# 2_-Charger.net
KiCad netlist of a schematic drawn in Altium Designer
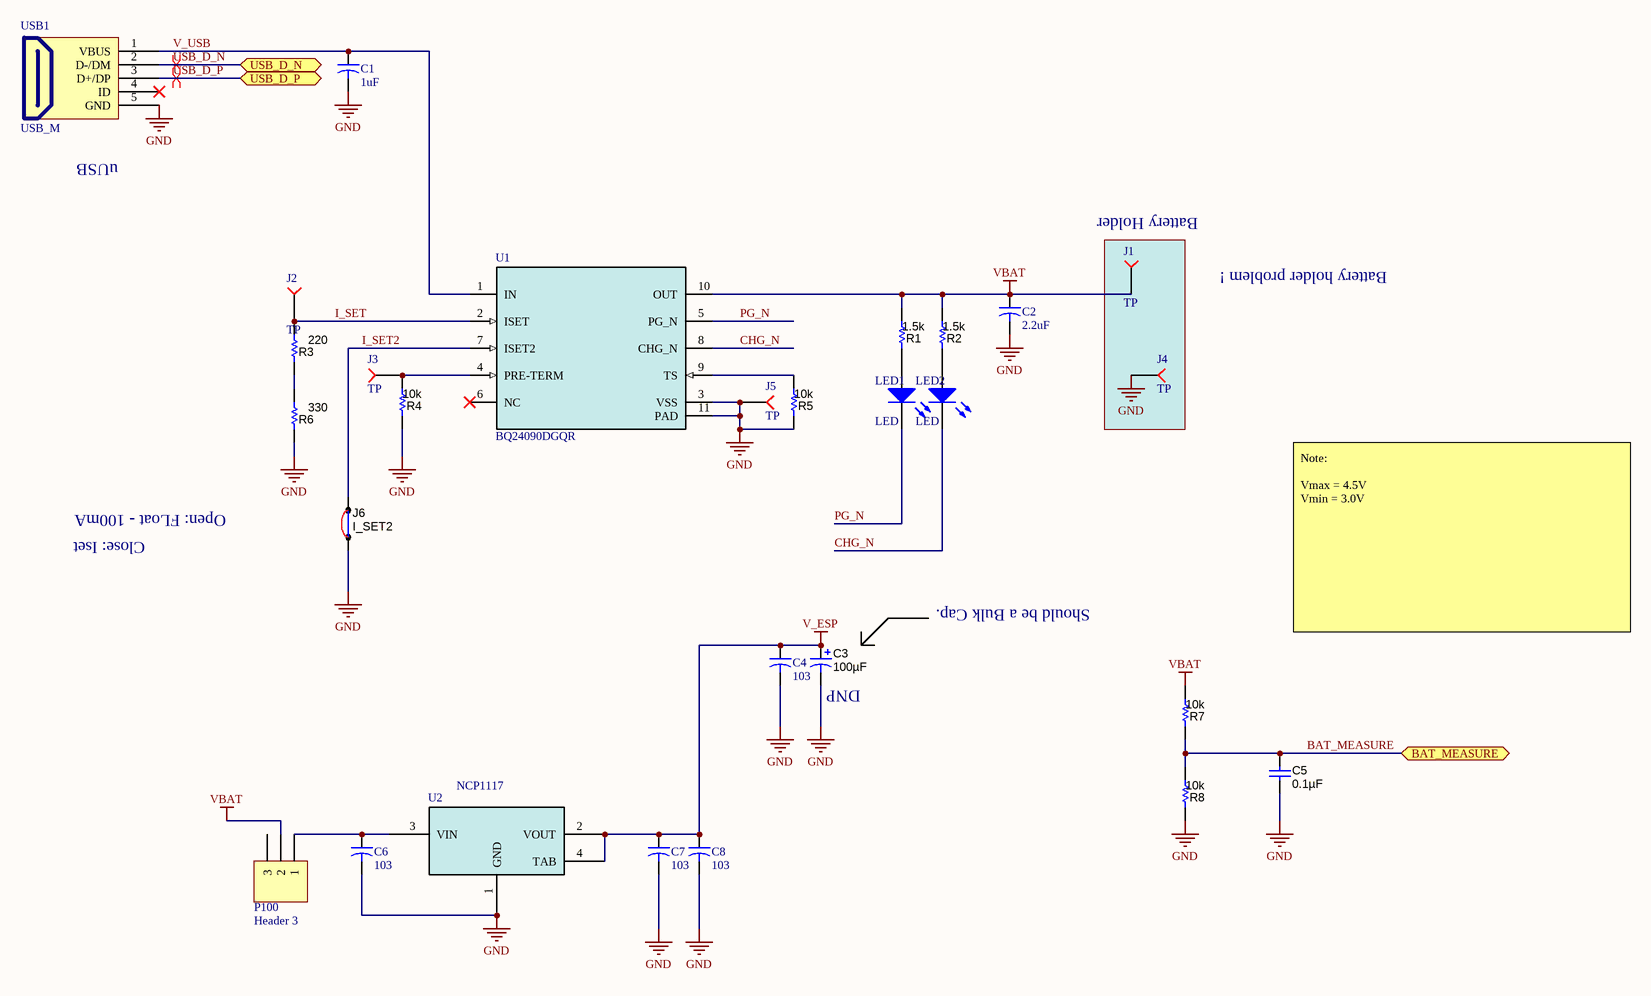
[diagram p0: [2]-Charger.SchDoc]

(export (version "E")
  (design (tool "Eeschema 10.0.6"))
  (components
    (comp (ref "C1")
      (value "1uF")
      (footprint "0603")
      (description "Ceramic")
      (fields (field (name "PUBLISHER") "Altium Limited"))
      (libsource (lib "Capacitor") (part "Cap 0805"))
    )
    (comp (ref "C2")
      (value "2.2uF")
      (footprint "0603")
      (description "Ceramic")
      (fields (field (name "PUBLISHER") "Altium Limited"))
      (libsource (lib "Capacitor") (part "Cap 0805"))
    )
    (comp (ref "C3")
      (value "293D107X96R3B2TE3")
      (footprint "3528-21")
      (description "CAP, TANT, 100uF, 6.3V, +/-10%, 1.7 ohm, 3528-21 SMD")
      (fields
        (field (name "MANUFACTURER") "Vishay-Sprague")
        (field (name "VALUEDISPLAYED") "100µF")
        (field (name "PUBLISHER") "Texas Instruments")
      )
      (libsource (lib "tuongpv2") (part "C_293D107X96R3B2TE3"))
    )
    (comp (ref "C4")
      (value "103")
      (footprint "0603")
      (description "Ceramic")
      (fields (field (name "PUBLISHER") "Altium Limited"))
      (libsource (lib "Capacitor") (part "Cap 0805"))
    )
    (comp (ref "C5")
      (value "0603YC104JAT2A")
      (footprint "0603")
      (description "CAP, CERM, 0.1uF, 16V, +/-5%, X7R, 0603")
      (fields
        (field (name "MANUFACTURER") "AVX")
        (field (name "VALUEDISPLAYED") "0.1µF")
        (field (name "PUBLISHER") "Texas Instruments")
      )
      (libsource (lib "tuongpv2") (part "Cap_0603"))
    )
    (comp (ref "C6")
      (value "103")
      (footprint "0603")
      (description "Ceramic")
      (fields (field (name "PUBLISHER") "Altium Limited"))
      (libsource (lib "Capacitor") (part "Cap 0805"))
    )
    (comp (ref "C7")
      (value "103")
      (footprint "0603")
      (description "Ceramic")
      (fields (field (name "PUBLISHER") "Altium Limited"))
      (libsource (lib "Capacitor") (part "Cap 0805"))
    )
    (comp (ref "C8")
      (value "103")
      (footprint "0603")
      (description "Ceramic")
      (fields (field (name "PUBLISHER") "Altium Limited"))
      (libsource (lib "Capacitor") (part "Cap 0805"))
    )
    (comp (ref "J1")
      (value "TP")
      (footprint "TP")
      (description "Test point (true)")
      (libsource (lib "Cty1") (part "TP"))
    )
    (comp (ref "J2")
      (value "TP")
      (footprint "TP")
      (description "Test point (true)")
      (libsource (lib "Cty1") (part "TP"))
    )
    (comp (ref "J3")
      (value "TP")
      (footprint "TP")
      (description "Test point (true)")
      (libsource (lib "Cty1") (part "TP"))
    )
    (comp (ref "J4")
      (value "TP")
      (footprint "TP")
      (description "Test point (true)")
      (libsource (lib "Cty1") (part "TP"))
    )
    (comp (ref "J5")
      (value "TP")
      (footprint "TP")
      (description "Test point (true)")
      (libsource (lib "Cty1") (part "TP"))
    )
    (comp (ref "J6")
      (value "I_SET2")
      (footprint "HDR1X2")
      (description "Jumper Wire, 200mil spacing, Red, pkg of 200")
      (fields
        (field (name "PARTNUMBER") "923345-02-C")
        (field (name "MANUFACTURER") "3M")
        (field (name "SYMBOLCREATOR") "a0412235")
        (field (name "PUBLISHER") "Texas Instruments")
      )
      (libsource (lib "Connectors") (part "923345-02-C"))
    )
    (comp (ref "LED1")
      (value "LED")
      (footprint "LED-0603-YELLOW")
      (description "Typical INFRARED GaAs LED")
      (fields (field (name "PUBLISHER") "Altium Limited"))
      (libsource (lib "VTEKLib") (part "LED"))
    )
    (comp (ref "LED2")
      (value "LED")
      (footprint "LED-0603-YELLOW")
      (description "Typical INFRARED GaAs LED")
      (fields (field (name "PUBLISHER") "Altium Limited"))
      (libsource (lib "VTEKLib") (part "LED"))
    )
    (comp (ref "P100")
      (value "Header 3")
      (footprint "SW_Slide")
      (description "Header, 3-Pin")
      (fields (field (name "PUBLISHER") "Altium Limited"))
      (libsource (lib "Connecter") (part "Header 3"))
    )
    (comp (ref "R1")
      (value "1.5k")
      (footprint "0603")
      (description "RES 5%, 0.125W, 0805")
      (fields
        (field (name "PARTNUMBER") "CRCW08051K00JNEA")
        (field (name "MANUFACTURER") "Vishay-Dale")
        (field (name "PUBLISHER") "Texas Instruments")
      )
      (libsource (lib "Cty1") (part "R0805_025W"))
    )
    (comp (ref "R2")
      (value "1.5k")
      (footprint "0603")
      (description "RES 5%, 0.125W, 0805")
      (fields
        (field (name "PARTNUMBER") "CRCW08051K00JNEA")
        (field (name "MANUFACTURER") "Vishay-Dale")
        (field (name "PUBLISHER") "Texas Instruments")
      )
      (libsource (lib "Cty1") (part "R0805_025W"))
    )
    (comp (ref "R3")
      (value "220")
      (footprint "0603")
      (description "RES 5%, 0.125W, 0805")
      (fields
        (field (name "PARTNUMBER") "CRCW08051K00JNEA")
        (field (name "MANUFACTURER") "Vishay-Dale")
        (field (name "PUBLISHER") "Texas Instruments")
      )
      (libsource (lib "Cty1") (part "R0805_025W"))
    )
    (comp (ref "R4")
      (value "10k")
      (footprint "0603")
      (description "RES 5%, 0.125W, 0805")
      (fields
        (field (name "PARTNUMBER") "CRCW08051K00JNEA")
        (field (name "MANUFACTURER") "Vishay-Dale")
        (field (name "PUBLISHER") "Texas Instruments")
      )
      (libsource (lib "Cty1") (part "R0805_025W"))
    )
    (comp (ref "R5")
      (value "10k")
      (footprint "0603")
      (description "RES 5%, 0.125W, 0805")
      (fields
        (field (name "PARTNUMBER") "CRCW08051K00JNEA")
        (field (name "MANUFACTURER") "Vishay-Dale")
        (field (name "PUBLISHER") "Texas Instruments")
      )
      (libsource (lib "Cty1") (part "R0805_025W"))
    )
    (comp (ref "R6")
      (value "330")
      (footprint "0603")
      (description "RES 5%, 0.125W, 0805")
      (fields
        (field (name "PARTNUMBER") "CRCW08051K00JNEA")
        (field (name "MANUFACTURER") "Vishay-Dale")
        (field (name "PUBLISHER") "Texas Instruments")
      )
      (libsource (lib "Cty1") (part "R0805_025W"))
    )
    (comp (ref "R7")
      (value "10k")
      (footprint "0603")
      (description "RES 5%, 0.125W, 0805")
      (fields
        (field (name "PARTNUMBER") "CRCW08051K00JNEA")
        (field (name "MANUFACTURER") "Vishay-Dale")
        (field (name "PUBLISHER") "Texas Instruments")
      )
      (libsource (lib "Cty1") (part "R0805_025W"))
    )
    (comp (ref "R8")
      (value "10k")
      (footprint "0603")
      (description "RES 5%, 0.125W, 0805")
      (fields
        (field (name "PARTNUMBER") "CRCW08051K00JNEA")
        (field (name "MANUFACTURER") "Vishay-Dale")
        (field (name "PUBLISHER") "Texas Instruments")
      )
      (libsource (lib "Cty1") (part "R0805_025W"))
    )
    (comp (ref "U1")
      (value "BQ24090DGQR")
      (footprint "DGQ0010D_NV_N")
      (description "Single Cell Li-Ion and Li-Pol Battery Charger")
      (fields
        (field (name "ALTERNATE PARTNUMBER") "BQ24090DGQT")
        (field (name "MANUFACTURER") "Texas Instruments")
      )
      (libsource (lib "SMPS_IC") (part "BQ24090DGQR"))
    )
    (comp (ref "U2")
      (value "NCP1117")
      (footprint "SOT-223B_L")
      (description "1000mA Low-Dropout Positive Fixed and Adjustable Voltage Regulators")
      (fields (field (name "DIGIKEY PART") "NCP1117ST33T3GOSTR-ND"))
      (libsource (lib "SMPS_IC") (part "NCP1117"))
    )
    (comp (ref "USB1") (value "USB_M") (footprint "USB_MICRO_SMD") (libsource (lib "VTEKLib") (part "USB_M")))
  )
  (nets
    (net (code "1") (name "/BAT_MEASURE") (class "Default")
      (node (ref "C5") (pin "1") (pinfunction "1_1") (pintype "passive"))
      (node (ref "R7") (pin "1") (pinfunction "1_1") (pintype "passive"))
      (node (ref "R8") (pin "2") (pinfunction "2_2") (pintype "passive"))
    )
    (net (code "2") (name "/CHG_N") (class "Default")
      (node (ref "LED2") (pin "2") (pinfunction "K_2") (pintype "passive"))
      (node (ref "U1") (pin "8") (pinfunction "CHG_N_8") (pintype "tri_state"))
    )
    (net (code "3") (name "/I_SET") (class "Default")
      (node (ref "J2") (pin "0") (pinfunction "0_0") (pintype "passive"))
      (node (ref "R3") (pin "2") (pinfunction "2_2") (pintype "passive"))
      (node (ref "U1") (pin "2") (pinfunction "ISET_2") (pintype "input"))
    )
    (net (code "4") (name "/I_SET2") (class "Default")
      (node (ref "J6") (pin "2") (pinfunction "2_2") (pintype "passive"))
      (node (ref "U1") (pin "7") (pinfunction "ISET2_7") (pintype "input"))
    )
    (net (code "5") (name "/PG_N") (class "Default")
      (node (ref "LED1") (pin "2") (pinfunction "K_2") (pintype "passive"))
      (node (ref "U1") (pin "5") (pinfunction "PG_N_5") (pintype "tri_state"))
    )
    (net (code "6") (name "/USB_D_N") (class "Default")
      (node (ref "USB1") (pin "2") (pinfunction "D-/DM_2") (pintype "passive"))
    )
    (net (code "7") (name "/USB_D_P") (class "Default")
      (node (ref "USB1") (pin "3") (pinfunction "D+/DP_3") (pintype "passive"))
    )
    (net (code "8") (name "/V_USB") (class "Default")
      (node (ref "C1") (pin "1") (pinfunction "1_1") (pintype "passive"))
      (node (ref "U1") (pin "1") (pinfunction "IN_1") (pintype "power_in"))
      (node (ref "USB1") (pin "1") (pinfunction "VBUS_1") (pintype "passive"))
    )
    (net (code "9") (name "GND") (class "Default")
      (node (ref "C1") (pin "2") (pinfunction "2_2") (pintype "passive"))
      (node (ref "C2") (pin "2") (pinfunction "2_2") (pintype "passive"))
      (node (ref "C3") (pin "2") (pinfunction "-_2") (pintype "passive"))
      (node (ref "C4") (pin "2") (pinfunction "2_2") (pintype "passive"))
      (node (ref "C5") (pin "2") (pinfunction "2_2") (pintype "passive"))
      (node (ref "C6") (pin "2") (pinfunction "2_2") (pintype "passive"))
      (node (ref "C7") (pin "2") (pinfunction "2_2") (pintype "passive"))
      (node (ref "C8") (pin "2") (pinfunction "2_2") (pintype "passive"))
      (node (ref "J4") (pin "0") (pinfunction "0_0") (pintype "passive"))
      (node (ref "J5") (pin "0") (pinfunction "0_0") (pintype "passive"))
      (node (ref "J6") (pin "1") (pinfunction "1_1") (pintype "passive"))
      (node (ref "R4") (pin "1") (pinfunction "1_1") (pintype "passive"))
      (node (ref "R5") (pin "1") (pinfunction "1_1") (pintype "passive"))
      (node (ref "R6") (pin "1") (pinfunction "1_1") (pintype "passive"))
      (node (ref "R8") (pin "1") (pinfunction "1_1") (pintype "passive"))
      (node (ref "U1") (pin "11") (pinfunction "PAD_11") (pintype "power_in"))
      (node (ref "U1") (pin "3") (pinfunction "VSS_3") (pintype "power_in"))
      (node (ref "U2") (pin "1") (pinfunction "GND_1") (pintype "passive"))
      (node (ref "USB1") (pin "5") (pinfunction "GND_5") (pintype "passive"))
    )
    (net (code "10") (name "Net-(LED1-A)") (class "Default")
      (node (ref "LED1") (pin "1") (pinfunction "A_1") (pintype "passive"))
      (node (ref "R1") (pin "1") (pinfunction "1_1") (pintype "passive"))
    )
    (net (code "11") (name "Net-(LED2-A)") (class "Default")
      (node (ref "LED2") (pin "1") (pinfunction "A_1") (pintype "passive"))
      (node (ref "R2") (pin "1") (pinfunction "1_1") (pintype "passive"))
    )
    (net (code "12") (name "Net-(R3-Pad1)") (class "Default")
      (node (ref "R3") (pin "1") (pinfunction "1_1") (pintype "passive"))
      (node (ref "R6") (pin "2") (pinfunction "2_2") (pintype "passive"))
    )
    (net (code "13") (name "Net-(U1-PRE-TERM)") (class "Default")
      (node (ref "J3") (pin "0") (pinfunction "0_0") (pintype "passive"))
      (node (ref "R4") (pin "2") (pinfunction "2_2") (pintype "passive"))
      (node (ref "U1") (pin "4") (pinfunction "PRE-TERM_4") (pintype "input"))
    )
    (net (code "14") (name "Net-(U1-TS)") (class "Default")
      (node (ref "R5") (pin "2") (pinfunction "2_2") (pintype "passive"))
      (node (ref "U1") (pin "9") (pinfunction "TS_9") (pintype "input"))
    )
    (net (code "15") (name "Net-(U2-VIN)") (class "Default")
      (node (ref "C6") (pin "1") (pinfunction "1_1") (pintype "passive"))
      (node (ref "P100") (pin "1") (pinfunction "1_1") (pintype "passive"))
      (node (ref "U2") (pin "3") (pinfunction "VIN_3") (pintype "passive"))
    )
    (net (code "16") (name "VBAT") (class "Default")
      (node (ref "C2") (pin "1") (pinfunction "1_1") (pintype "passive"))
      (node (ref "J1") (pin "0") (pinfunction "0_0") (pintype "passive"))
      (node (ref "P100") (pin "2") (pinfunction "2_2") (pintype "passive"))
      (node (ref "R1") (pin "2") (pinfunction "2_2") (pintype "passive"))
      (node (ref "R2") (pin "2") (pinfunction "2_2") (pintype "passive"))
      (node (ref "R7") (pin "2") (pinfunction "2_2") (pintype "passive"))
      (node (ref "U1") (pin "10") (pinfunction "OUT_10") (pintype "power_in"))
    )
    (net (code "17") (name "V_ESP") (class "Default")
      (node (ref "C3") (pin "1") (pinfunction "+_1") (pintype "passive"))
      (node (ref "C4") (pin "1") (pinfunction "1_1") (pintype "passive"))
      (node (ref "C7") (pin "1") (pinfunction "1_1") (pintype "passive"))
      (node (ref "C8") (pin "1") (pinfunction "1_1") (pintype "passive"))
      (node (ref "U2") (pin "2") (pinfunction "VOUT_2") (pintype "passive"))
      (node (ref "U2") (pin "4") (pinfunction "TAB_4") (pintype "power_in"))
    )
    (net (code "18") (name "unconnected-(P100-Pad3)") (class "Default")
      (node (ref "P100") (pin "3") (pinfunction "3_3") (pintype "passive"))
    )
    (net (code "19") (name "unconnected-(U1-NC-Pad6)") (class "Default")
      (node (ref "U1") (pin "6") (pinfunction "NC_6") (pintype "passive+no_connect"))
    )
    (net (code "20") (name "unconnected-(USB1-ID-Pad4)") (class "Default")
      (node (ref "USB1") (pin "4") (pinfunction "ID_4") (pintype "passive+no_connect"))
    )
  )
)
